# connectors.net
KiCad netlist of a schematic drawn in Altium Designer
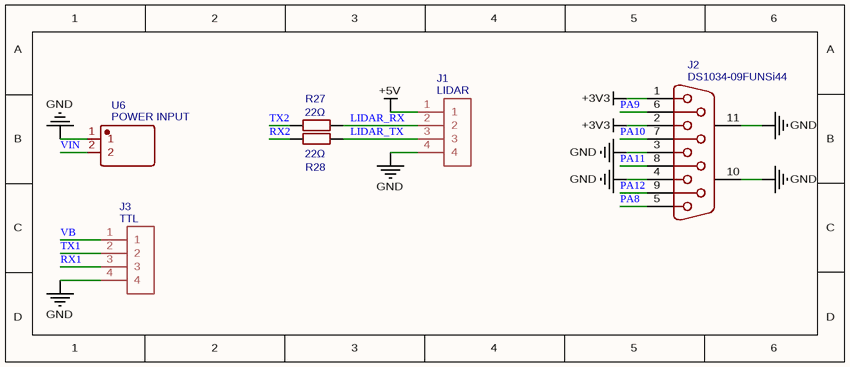
[diagram p0: connectors.schdoc]

(export (version "E")
  (design (tool "Eeschema 10.0.6"))
  (components
    (comp (ref "J1")
      (value "LIDAR")
      (fields (field (name "CONTRIBUTOR") "Nicola Lorenzini"))
      (libsource (lib "altium-import") (part "root_0_LIDAR_"))
    )
    (comp (ref "J2")
      (value "DS1034-09FUNSi44")
      (fields (field (name "MANUFACTURER") "CONNFLY") (field (name "CONTRIBUTOR") "LCSC"))
      (libsource (lib "altium-import") (part "root_0_DS1034-09FUNSi44_"))
    )
    (comp (ref "J3")
      (value "TTL")
      (fields (field (name "CONTRIBUTOR") "Nicola Lorenzini"))
      (libsource (lib "altium-import") (part "root_0_TTL_"))
    )
    (comp (ref "R27")
      (value "22Ω")
      (fields
        (field (name "MANUFACTURER") "UNI-ROYAL(厚声)")
        (field (name "MANUFACTURER PART") "0402WGF220JTCE")
      )
      (libsource (lib "altium-import") (part "root_0_22Ω_"))
    )
    (comp (ref "R28")
      (value "22Ω")
      (fields
        (field (name "MANUFACTURER") "UNI-ROYAL(厚声)")
        (field (name "MANUFACTURER PART") "0402WGF220JTCE")
      )
      (libsource (lib "altium-import") (part "root_0_22Ω_"))
    )
    (comp (ref "U6")
      (value "POWER INPUT")
      (fields
        (field (name "MANUFACTURER") "JST")
        (field (name "MANUFACTURER PART") "B2B-XH-A-GU")
        (field (name "CONTRIBUTOR") "LCSC")
      )
      (libsource (lib "altium-import") (part "root_0_POWER INPUT_"))
    )
  )
  (nets
    (net (code "1") (name "+3V3") (class "Default")
      (node (ref "J2") (pin "1") (pinfunction "1_1") (pintype "passive"))
      (node (ref "J2") (pin "2") (pinfunction "2_2") (pintype "passive"))
    )
    (net (code "2") (name "+5V") (class "Default")
      (node (ref "J1") (pin "1") (pinfunction "1_1") (pintype "passive"))
    )
    (net (code "3") (name "/LIDAR_RX") (class "Default")
      (node (ref "J1") (pin "2") (pinfunction "2_2") (pintype "passive"))
      (node (ref "R27") (pin "2") (pinfunction "2_2") (pintype "passive"))
    )
    (net (code "4") (name "/LIDAR_TX") (class "Default")
      (node (ref "J1") (pin "3") (pinfunction "3_3") (pintype "passive"))
      (node (ref "R28") (pin "2") (pinfunction "2_2") (pintype "passive"))
    )
    (net (code "5") (name "/PA8") (class "Default")
      (node (ref "J2") (pin "5") (pinfunction "5_5") (pintype "passive"))
    )
    (net (code "6") (name "/PA9") (class "Default")
      (node (ref "J2") (pin "6") (pinfunction "6_6") (pintype "passive"))
    )
    (net (code "7") (name "/PA10") (class "Default")
      (node (ref "J2") (pin "7") (pinfunction "7_7") (pintype "passive"))
    )
    (net (code "8") (name "/PA11") (class "Default")
      (node (ref "J2") (pin "8") (pinfunction "8_8") (pintype "passive"))
    )
    (net (code "9") (name "/PA12") (class "Default")
      (node (ref "J2") (pin "9") (pinfunction "9_9") (pintype "passive"))
    )
    (net (code "10") (name "/RX1") (class "Default")
      (node (ref "J3") (pin "3") (pinfunction "3_3") (pintype "passive"))
    )
    (net (code "11") (name "/RX2") (class "Default")
      (node (ref "R28") (pin "1") (pinfunction "1_1") (pintype "passive"))
    )
    (net (code "12") (name "/TX1") (class "Default")
      (node (ref "J3") (pin "2") (pinfunction "2_2") (pintype "passive"))
    )
    (net (code "13") (name "/TX2") (class "Default")
      (node (ref "R27") (pin "1") (pinfunction "1_1") (pintype "passive"))
    )
    (net (code "14") (name "/VB") (class "Default")
      (node (ref "J3") (pin "1") (pinfunction "1_1") (pintype "passive"))
    )
    (net (code "15") (name "/VIN") (class "Default")
      (node (ref "U6") (pin "2") (pinfunction "2_2") (pintype "passive"))
    )
    (net (code "16") (name "GND") (class "Default")
      (node (ref "J1") (pin "4") (pinfunction "4_4") (pintype "passive"))
      (node (ref "J2") (pin "10") (pinfunction "MH1_10") (pintype "passive"))
      (node (ref "J2") (pin "11") (pinfunction "MH2_11") (pintype "passive"))
      (node (ref "J2") (pin "3") (pinfunction "3_3") (pintype "passive"))
      (node (ref "J2") (pin "4") (pinfunction "4_4") (pintype "passive"))
      (node (ref "J3") (pin "4") (pinfunction "4_4") (pintype "passive"))
      (node (ref "U6") (pin "1") (pinfunction "1_1") (pintype "passive"))
    )
  )
)
